# Schematic_easyEDA_-_openELECTRO_-_ARDUIN.net
KiCad netlist of a schematic drawn in EasyEDA
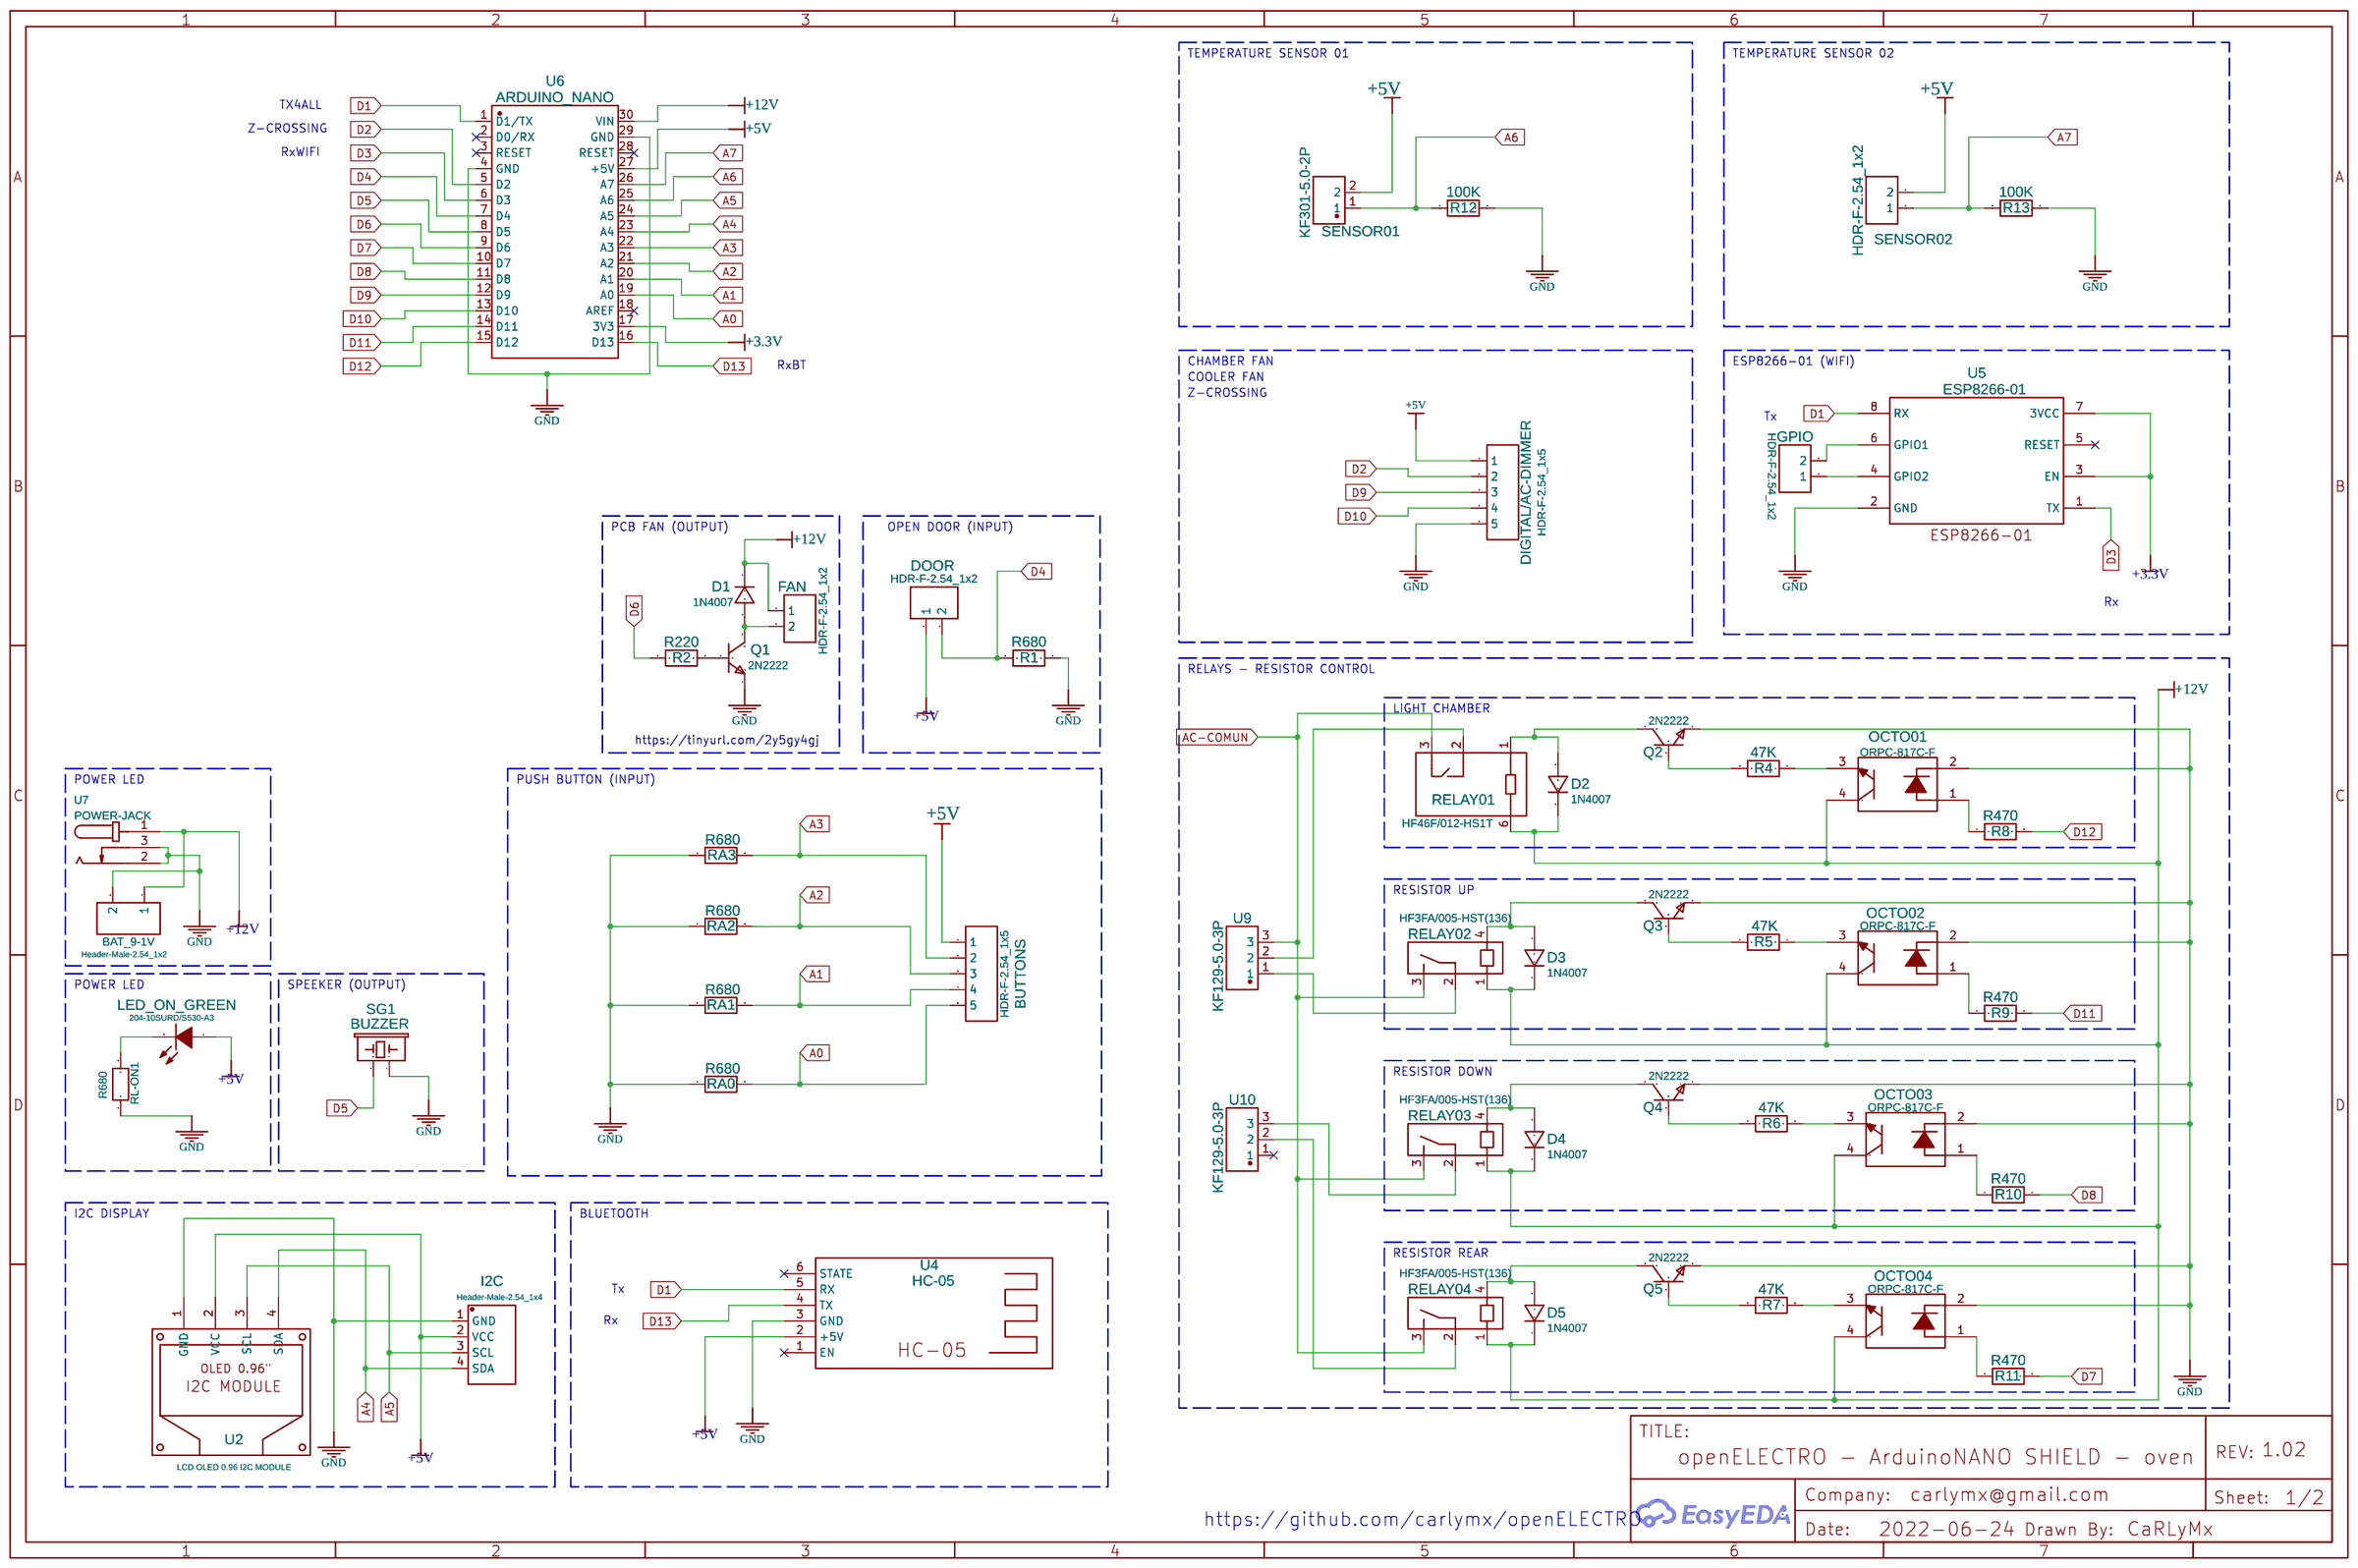
[diagram p0: openELECTRO - ARDUINO NANO SHIELD v1.02]
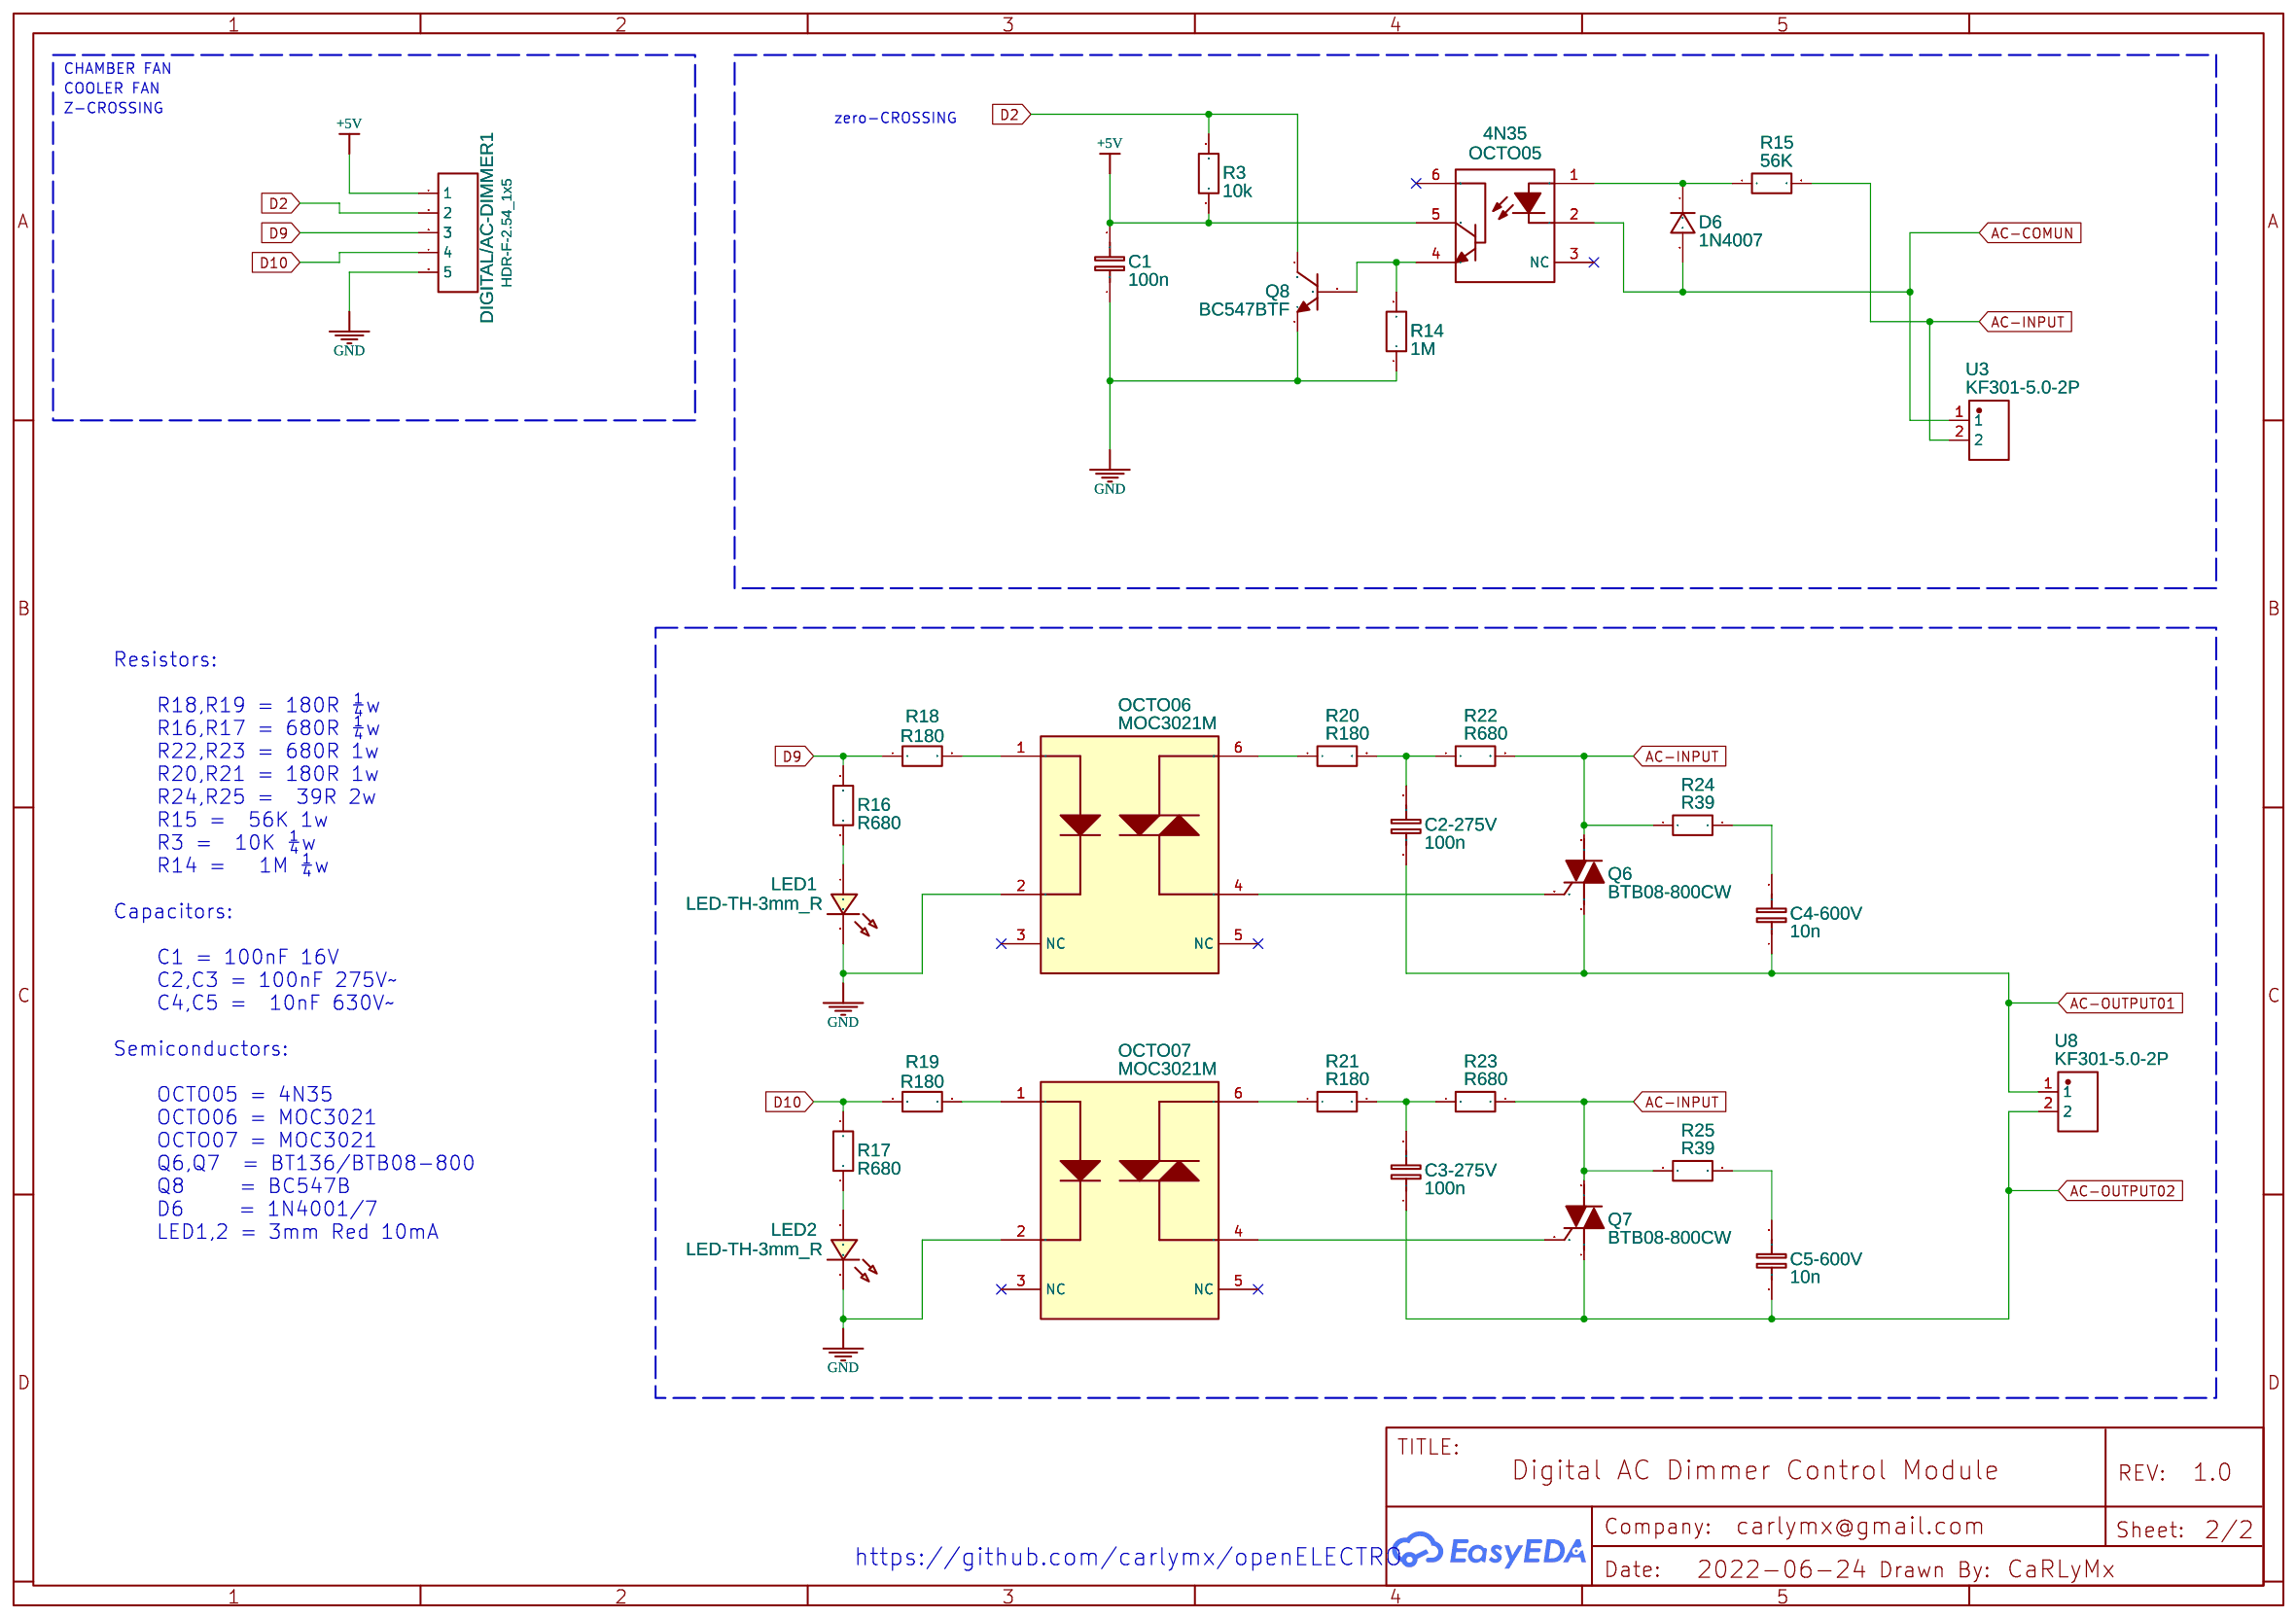
[diagram p1: openELECTRO - Digital AC Dimmer Control v1.0]

(export (version "E")
  (design (tool "Eeschema 10.0.6"))
  (components
    (comp (ref "BAT_9-1V")
      (value "Header-Male-2.54_1x2")
      (fields (field (name "BOM_Manufacturer Part") "826629-2") (field (name "BOM_Supplier Part") "C86471"))
      (libsource (lib "") (part "Unknown_65_-400"))
    )
    (comp (ref "BUTTONS")
      (value "HDR-F-2.54_1x5")
      (fields (field (name "BOM_Supplier Part") "C50950"))
      (libsource (lib "") (part "HDR-F-2.54_1x5"))
    )
    (comp (ref "D1")
      (value "1N4007")
      (fields (field (name "BOM_Supplier Part") "C106903"))
      (libsource (lib "") (part "1N4007_1"))
    )
    (comp (ref "D2")
      (value "1N4007")
      (fields (field (name "BOM_Supplier Part") "C106903"))
      (libsource (lib "") (part "1N4007"))
    )
    (comp (ref "D3")
      (value "1N4007")
      (fields (field (name "BOM_Supplier Part") "C106903"))
      (libsource (lib "") (part "1N4007"))
    )
    (comp (ref "D4")
      (value "1N4007")
      (fields (field (name "BOM_Supplier Part") "C106903"))
      (libsource (lib "") (part "1N4007"))
    )
    (comp (ref "D5")
      (value "1N4007")
      (fields (field (name "BOM_Supplier Part") "C106903"))
      (libsource (lib "") (part "1N4007"))
    )
    (comp (ref "DIGITAL/AC-DIMMER")
      (value "HDR-F-2.54_1x5")
      (fields (field (name "BOM_Supplier Part") "C50950"))
      (libsource (lib "") (part "HDR-F-2.54_1x5_1"))
    )
    (comp (ref "DOOR")
      (value "HDR-F-2.54_1x2")
      (fields (field (name "BOM_Supplier Part") "C49661"))
      (libsource (lib "") (part "HDR-F-2.54_1x2"))
    )
    (comp (ref "FAN")
      (value "HDR-F-2.54_1x2")
      (fields (field (name "BOM_Supplier Part") "C49661"))
      (libsource (lib "") (part "HDR-F-2.54_1x2_1"))
    )
    (comp (ref "GPIO")
      (value "HDR-F-2.54_1x2")
      (fields (field (name "BOM_Supplier Part") "C49661"))
      (libsource (lib "") (part "HDR-F-2.54_1x2_3"))
    )
    (comp (ref "I2C")
      (value "Header-Male-2.54_1x4")
      (fields
        (field (name "BOM_Manufacturer Part") "210S-1*4P L=11.6MMGold-plated black")
        (field (name "BOM_Supplier Part") "C124378")
      )
      (libsource (lib "") (part "Unknown_290_-125"))
    )
    (comp (ref "LED_ON_GREEN")
      (value "204-10SURD/S530-A3")
      (fields (field (name "BOM_Supplier Part") "C99772"))
      (libsource (lib "") (part "Unknown_100_-315"))
    )
    (comp (ref "OCTO01")
      (value "ORPC-817C-F")
      (fields (field (name "BOM_Supplier Part") "C2842770"))
      (libsource (lib "") (part "ORPC-817C-F"))
    )
    (comp (ref "OCTO02")
      (value "ORPC-817C-F")
      (fields (field (name "BOM_Supplier Part") "C2842770"))
      (libsource (lib "") (part "ORPC-817C-F"))
    )
    (comp (ref "OCTO03")
      (value "ORPC-817C-F")
      (fields (field (name "BOM_Supplier Part") "C2842770"))
      (libsource (lib "") (part "ORPC-817C-F"))
    )
    (comp (ref "OCTO04")
      (value "ORPC-817C-F")
      (fields (field (name "BOM_Supplier Part") "C2842770"))
      (libsource (lib "") (part "ORPC-817C-F"))
    )
    (comp (ref "Q1")
      (value "2N2222")
      (fields (field (name "BOM_Supplier Part") "C118536"))
      (libsource (lib "") (part "2N2222_1"))
    )
    (comp (ref "Q2")
      (value "2N2222")
      (fields (field (name "BOM_Supplier Part") "C118536"))
      (libsource (lib "") (part "2N2222"))
    )
    (comp (ref "Q3")
      (value "2N2222")
      (fields (field (name "BOM_Supplier Part") "C118536"))
      (libsource (lib "") (part "2N2222"))
    )
    (comp (ref "Q4")
      (value "2N2222")
      (fields (field (name "BOM_Supplier Part") "C118536"))
      (libsource (lib "") (part "2N2222"))
    )
    (comp (ref "Q5")
      (value "2N2222")
      (fields (field (name "BOM_Supplier Part") "C118536"))
      (libsource (lib "") (part "2N2222"))
    )
    (comp (ref "R1") (value "R680") (libsource (lib "") (part "R_0603_EU_1")))
    (comp (ref "R2") (value "R220") (libsource (lib "") (part "R_0603_EU")))
    (comp (ref "R4") (value "47K") (libsource (lib "") (part "R_0603_EU_1")))
    (comp (ref "R5") (value "47K") (libsource (lib "") (part "R_0603_EU")))
    (comp (ref "R6") (value "47K") (libsource (lib "") (part "R_0603_EU")))
    (comp (ref "R7") (value "47K") (libsource (lib "") (part "R_0603_EU")))
    (comp (ref "R8") (value "R470") (libsource (lib "") (part "R_0603_EU")))
    (comp (ref "R9") (value "R470") (libsource (lib "") (part "R_0603_EU")))
    (comp (ref "R10") (value "R470") (libsource (lib "") (part "R_0603_EU")))
    (comp (ref "R11") (value "R470") (libsource (lib "") (part "R_0603_EU")))
    (comp (ref "R12") (value "100K") (libsource (lib "") (part "R_0603_EU")))
    (comp (ref "R13") (value "100K") (libsource (lib "") (part "R_0603_EU")))
    (comp (ref "RA0") (value "R680") (libsource (lib "") (part "Res_AXIAL-0.3(1/8W)_EU")))
    (comp (ref "RA1") (value "R680") (libsource (lib "") (part "Res_AXIAL-0.3(1/8W)_EU")))
    (comp (ref "RA2") (value "R680") (libsource (lib "") (part "Res_AXIAL-0.3(1/8W)_EU")))
    (comp (ref "RA3") (value "R680") (libsource (lib "") (part "Res_AXIAL-0.3(1/8W)_EU")))
    (comp (ref "RELAY01")
      (value "HF46F/012-HS1T")
      (fields (field (name "BOM_Supplier Part") "C2976852"))
      (libsource (lib "") (part "HF46F/012-HS1T"))
    )
    (comp (ref "RELAY02")
      (value "HF3FA/005-HST(136)")
      (fields (field (name "BOM_Supplier Part") "C712707"))
      (libsource (lib "") (part "HF3FA/005-HST(136)"))
    )
    (comp (ref "RELAY03")
      (value "HF3FA/005-HST(136)")
      (fields (field (name "BOM_Supplier Part") "C712707"))
      (libsource (lib "") (part "HF3FA/005-HST(136)"))
    )
    (comp (ref "RELAY04")
      (value "HF3FA/005-HST(136)")
      (fields (field (name "BOM_Supplier Part") "C712707"))
      (libsource (lib "") (part "HF3FA/005-HST(136)"))
    )
    (comp (ref "RL-ON1") (value "R680") (libsource (lib "") (part "Res_AXIAL-0.3(1/8W)_EU_1")))
    (comp (ref "SENSOR01")
      (value "KF301-5.0-2P")
      (fields (field (name "BOM_Supplier Part") "C474881"))
      (libsource (lib "") (part "KF301-5.0-2P"))
    )
    (comp (ref "SENSOR02")
      (value "HDR-F-2.54_1x2")
      (fields (field (name "BOM_Supplier Part") "C49661"))
      (libsource (lib "") (part "HDR-F-2.54_1x2_2"))
    )
    (comp (ref "SG1") (value "BUZZER") (libsource (lib "") (part "Unknown_225_-305")))
    (comp (ref "U2")
      (value "LCD OLED 0.96 I2C MODULE")
      (fields (field (name "BOM_Manufacturer Part") "Control Chip SSD1306"))
      (libsource (lib "") (part "Unknown_80_-135"))
    )
    (comp (ref "U4") (value "HC-05") (libsource (lib "") (part "Unknown_500_-180")))
    (comp (ref "U5") (value "ESP8266-01") (libsource (lib "") (part "ESP8266-01")))
    (comp (ref "U6")
      (value "ARDUINO_NANO")
      (fields (field (name "BOM_Supplier Part") "C9900017879"))
      (libsource (lib "") (part "ARDUINO_NANO"))
    )
    (comp (ref "U7")
      (value "POWER-JACK")
      (fields (field (name "BOM_Supplier Part") "C9900001795"))
      (libsource (lib "") (part "POWER-JACK"))
    )
    (comp (ref "U9")
      (value "KF129-5.0-3P")
      (fields (field (name "BOM_Supplier Part") "C475091"))
      (libsource (lib "") (part "KF129-5.0-3P"))
    )
    (comp (ref "U10")
      (value "KF129-5.0-3P")
      (fields (field (name "BOM_Supplier Part") "C475091"))
      (libsource (lib "") (part "KF129-5.0-3P"))
    )
    (comp (ref "C1") (value "100n") (libsource (lib "") (part "C_0603_EU_1")))
    (comp (ref "C2-275V") (value "100n") (libsource (lib "") (part "C_0603_EU_4")))
    (comp (ref "C3-275V") (value "100n") (libsource (lib "") (part "C_0603_EU")))
    (comp (ref "C4-600V") (value "10n") (libsource (lib "") (part "C_0603_EU_2")))
    (comp (ref "C5-600V") (value "10n") (libsource (lib "") (part "C_0603_EU_3")))
    (comp (ref "D6")
      (value "1N4007")
      (fields (field (name "BOM_Supplier Part") "C106903"))
      (libsource (lib "") (part "1N4007"))
    )
    (comp (ref "DIGITAL/AC-DIMMER1")
      (value "HDR-F-2.54_1x5")
      (fields (field (name "BOM_Supplier Part") "C50950"))
      (libsource (lib "") (part "HDR-F-2.54_1x5"))
    )
    (comp (ref "LED1")
      (value "LED-TH-3mm_R")
      (fields
        (field (name "BOM_Manufacturer Part") "204-10SDRD/S530-A3-L")
        (field (name "BOM_Supplier Part") "C84774")
      )
      (libsource (lib "") (part "LED-TH-3mm_R"))
    )
    (comp (ref "LED2")
      (value "LED-TH-3mm_R")
      (fields
        (field (name "BOM_Manufacturer Part") "204-10SDRD/S530-A3-L")
        (field (name "BOM_Supplier Part") "C84774")
      )
      (libsource (lib "") (part "LED-TH-3mm_R"))
    )
    (comp (ref "OCTO05")
      (value "4N35")
      (fields (field (name "BOM_Supplier Part") "C57084"))
      (libsource (lib "") (part "4N35"))
    )
    (comp (ref "OCTO06")
      (value "MOC3021M")
      (fields (field (name "BOM_Supplier Part") "C5242"))
      (libsource (lib "") (part "MOC3021M"))
    )
    (comp (ref "OCTO07")
      (value "MOC3021M")
      (fields (field (name "BOM_Supplier Part") "C5242"))
      (libsource (lib "") (part "MOC3021M"))
    )
    (comp (ref "Q6")
      (value "BTB08-800CW")
      (fields (field (name "BOM_Supplier Part") "C2900905"))
      (libsource (lib "") (part "BTB08-800CW"))
    )
    (comp (ref "Q7")
      (value "BTB08-800CW")
      (fields (field (name "BOM_Supplier Part") "C2900905"))
      (libsource (lib "") (part "BTB08-800CW"))
    )
    (comp (ref "Q8")
      (value "BC547BTF")
      (fields (field (name "BOM_Supplier Part") "C900798"))
      (libsource (lib "") (part "BC547BTF"))
    )
    (comp (ref "R3") (value "10k") (libsource (lib "") (part "R_AXIAL-0.3_EU_1")))
    (comp (ref "R14") (value "1M") (libsource (lib "") (part "R_AXIAL-0.3_EU_1")))
    (comp (ref "R15") (value "56K") (libsource (lib "") (part "R_AXIAL-0.3_EU")))
    (comp (ref "R16") (value "R680") (libsource (lib "") (part "R_AXIAL-0.3_EU_1")))
    (comp (ref "R17") (value "R680") (libsource (lib "") (part "R_AXIAL-0.3_EU_1")))
    (comp (ref "R18") (value "R180") (libsource (lib "") (part "R_AXIAL-0.3_EU")))
    (comp (ref "R19") (value "R180") (libsource (lib "") (part "R_AXIAL-0.3_EU")))
    (comp (ref "R20") (value "R180") (libsource (lib "") (part "R_AXIAL-0.3_EU")))
    (comp (ref "R21") (value "R180") (libsource (lib "") (part "R_AXIAL-0.3_EU")))
    (comp (ref "R22") (value "R680") (libsource (lib "") (part "R_AXIAL-0.3_EU")))
    (comp (ref "R23") (value "R680") (libsource (lib "") (part "R_AXIAL-0.3_EU")))
    (comp (ref "R24") (value "R39") (libsource (lib "") (part "R_AXIAL-0.3_EU")))
    (comp (ref "R25") (value "R39") (libsource (lib "") (part "R_AXIAL-0.3_EU")))
    (comp (ref "U3")
      (value "KF301-5.0-2P")
      (fields (field (name "BOM_Supplier Part") "C474881"))
      (libsource (lib "") (part "KF301-5.0-2P"))
    )
    (comp (ref "U8")
      (value "KF301-5.0-2P")
      (fields (field (name "BOM_Supplier Part") "C474881"))
      (libsource (lib "") (part "KF301-5.0-2P"))
    )
  )
  (nets
    (net (code "1") (name "+3.3V") (class "Default")
      (node (ref "U5") (pin "3") (pinfunction "EN_3") (pintype "unspecified"))
      (node (ref "U5") (pin "7") (pinfunction "3VCC_7") (pintype "unspecified"))
      (node (ref "U6") (pin "17") (pinfunction "3V3_17") (pintype "unspecified"))
    )
    (net (code "2") (name "+5V") (class "Default")
      (node (ref "BUTTONS") (pin "1") (pinfunction "1_1") (pintype "unspecified"))
      (node (ref "C1") (pin "2") (pinfunction "2_2") (pintype "unspecified"))
      (node (ref "DIGITAL/AC-DIMMER") (pin "1") (pinfunction "1_1") (pintype "unspecified"))
      (node (ref "DIGITAL/AC-DIMMER1") (pin "1") (pinfunction "1_1") (pintype "unspecified"))
      (node (ref "DOOR") (pin "1") (pinfunction "1_1") (pintype "input"))
      (node (ref "I2C") (pin "2") (pinfunction "VCC_2") (pintype "unspecified"))
      (node (ref "LED_ON_GREEN") (pin "1") (pinfunction "A_1") (pintype "unspecified"))
      (node (ref "OCTO05") (pin "5") (pinfunction "5_5") (pintype "unspecified"))
      (node (ref "R3") (pin "1") (pinfunction "1_1") (pintype "unspecified"))
      (node (ref "SENSOR01") (pin "2") (pinfunction "2_2") (pintype "unspecified"))
      (node (ref "SENSOR02") (pin "2") (pinfunction "2_2") (pintype "input"))
      (node (ref "U2") (pin "2") (pinfunction "VCC_2") (pintype "unspecified"))
      (node (ref "U4") (pin "2") (pinfunction "+5V_2") (pintype "unspecified"))
      (node (ref "U6") (pin "27") (pinfunction "+5V_27") (pintype "unspecified"))
    )
    (net (code "3") (name "+12V") (class "Default")
      (node (ref "BAT_9-1V") (pin "1") (pinfunction "1_1") (pintype "unspecified"))
      (node (ref "D1") (pin "1") (pinfunction "1_1") (pintype "unspecified"))
      (node (ref "D2") (pin "1") (pinfunction "1_1") (pintype "unspecified"))
      (node (ref "D3") (pin "1") (pinfunction "1_1") (pintype "unspecified"))
      (node (ref "D4") (pin "1") (pinfunction "1_1") (pintype "unspecified"))
      (node (ref "D5") (pin "1") (pinfunction "1_1") (pintype "unspecified"))
      (node (ref "FAN") (pin "1") (pinfunction "1_1") (pintype "input"))
      (node (ref "OCTO01") (pin "4") (pinfunction "4_4") (pintype "unspecified"))
      (node (ref "OCTO02") (pin "4") (pinfunction "4_4") (pintype "unspecified"))
      (node (ref "OCTO03") (pin "4") (pinfunction "4_4") (pintype "unspecified"))
      (node (ref "OCTO04") (pin "4") (pinfunction "4_4") (pintype "unspecified"))
      (node (ref "RELAY01") (pin "6") (pinfunction "6_6") (pintype "unspecified"))
      (node (ref "RELAY02") (pin "1") (pinfunction "1_1") (pintype "unspecified"))
      (node (ref "RELAY03") (pin "1") (pinfunction "1_1") (pintype "unspecified"))
      (node (ref "RELAY04") (pin "1") (pinfunction "1_1") (pintype "unspecified"))
      (node (ref "U6") (pin "30") (pinfunction "VIN_30") (pintype "unspecified"))
      (node (ref "U7") (pin "1") (pinfunction "1_1") (pintype "unspecified"))
    )
    (net (code "4") (name "A0") (class "Default")
      (node (ref "BUTTONS") (pin "5") (pinfunction "5_5") (pintype "unspecified"))
      (node (ref "RA0") (pin "2") (pinfunction "2_2") (pintype "unspecified"))
      (node (ref "U6") (pin "19") (pinfunction "A0_19") (pintype "unspecified"))
    )
    (net (code "5") (name "A1") (class "Default")
      (node (ref "BUTTONS") (pin "4") (pinfunction "4_4") (pintype "unspecified"))
      (node (ref "RA1") (pin "2") (pinfunction "2_2") (pintype "unspecified"))
      (node (ref "U6") (pin "20") (pinfunction "A1_20") (pintype "unspecified"))
    )
    (net (code "6") (name "A2") (class "Default")
      (node (ref "BUTTONS") (pin "3") (pinfunction "3_3") (pintype "unspecified"))
      (node (ref "RA2") (pin "2") (pinfunction "2_2") (pintype "unspecified"))
      (node (ref "U6") (pin "21") (pinfunction "A2_21") (pintype "unspecified"))
    )
    (net (code "7") (name "A3") (class "Default")
      (node (ref "BUTTONS") (pin "2") (pinfunction "2_2") (pintype "unspecified"))
      (node (ref "RA3") (pin "2") (pinfunction "2_2") (pintype "unspecified"))
      (node (ref "U6") (pin "22") (pinfunction "A3_22") (pintype "unspecified"))
    )
    (net (code "8") (name "A4") (class "Default")
      (node (ref "I2C") (pin "4") (pinfunction "SDA_4") (pintype "unspecified"))
      (node (ref "U2") (pin "4") (pinfunction "SDA_4") (pintype "unspecified"))
      (node (ref "U6") (pin "23") (pinfunction "A4_23") (pintype "unspecified"))
    )
    (net (code "9") (name "A5") (class "Default")
      (node (ref "I2C") (pin "3") (pinfunction "SCL_3") (pintype "unspecified"))
      (node (ref "U2") (pin "3") (pinfunction "SCL_3") (pintype "unspecified"))
      (node (ref "U6") (pin "24") (pinfunction "A5_24") (pintype "unspecified"))
    )
    (net (code "10") (name "A6") (class "Default")
      (node (ref "R12") (pin "1") (pinfunction "1_1") (pintype "unspecified"))
      (node (ref "SENSOR01") (pin "1") (pinfunction "1_1") (pintype "unspecified"))
      (node (ref "U6") (pin "25") (pinfunction "A6_25") (pintype "unspecified"))
    )
    (net (code "11") (name "A7") (class "Default")
      (node (ref "R13") (pin "1") (pinfunction "1_1") (pintype "unspecified"))
      (node (ref "SENSOR02") (pin "1") (pinfunction "1_1") (pintype "input"))
      (node (ref "U6") (pin "26") (pinfunction "A7_26") (pintype "unspecified"))
    )
    (net (code "12") (name "AC-COMUN") (class "Default")
      (node (ref "D6") (pin "2") (pinfunction "2_2") (pintype "unspecified"))
      (node (ref "OCTO05") (pin "2") (pinfunction "2_2") (pintype "unspecified"))
      (node (ref "RELAY01") (pin "3") (pinfunction "3_3") (pintype "unspecified"))
      (node (ref "RELAY02") (pin "3") (pinfunction "3_3") (pintype "unspecified"))
      (node (ref "RELAY03") (pin "3") (pinfunction "3_3") (pintype "unspecified"))
      (node (ref "RELAY04") (pin "3") (pinfunction "3_3") (pintype "unspecified"))
      (node (ref "U3") (pin "1") (pinfunction "1_1") (pintype "unspecified"))
      (node (ref "U9") (pin "3") (pinfunction "3_3") (pintype "unspecified"))
    )
    (net (code "13") (name "AC-INPUT") (class "Default")
      (node (ref "Q6") (pin "2") (pinfunction "T2_2") (pintype "unspecified"))
      (node (ref "Q7") (pin "2") (pinfunction "T2_2") (pintype "unspecified"))
      (node (ref "R15") (pin "2") (pinfunction "2_2") (pintype "unspecified"))
      (node (ref "R22") (pin "2") (pinfunction "2_2") (pintype "unspecified"))
      (node (ref "R23") (pin "2") (pinfunction "2_2") (pintype "unspecified"))
      (node (ref "R24") (pin "1") (pinfunction "1_1") (pintype "unspecified"))
      (node (ref "R25") (pin "1") (pinfunction "1_1") (pintype "unspecified"))
      (node (ref "U3") (pin "2") (pinfunction "2_2") (pintype "unspecified"))
    )
    (net (code "14") (name "AC-OUTPUT01") (class "Default")
      (node (ref "C2-275V") (pin "1") (pinfunction "1_1") (pintype "unspecified"))
      (node (ref "C4-600V") (pin "1") (pinfunction "1_1") (pintype "unspecified"))
      (node (ref "Q6") (pin "1") (pinfunction "T1_1") (pintype "unspecified"))
      (node (ref "U8") (pin "1") (pinfunction "1_1") (pintype "unspecified"))
    )
    (net (code "15") (name "AC-OUTPUT02") (class "Default")
      (node (ref "C3-275V") (pin "1") (pinfunction "1_1") (pintype "unspecified"))
      (node (ref "C5-600V") (pin "1") (pinfunction "1_1") (pintype "unspecified"))
      (node (ref "Q7") (pin "1") (pinfunction "T1_1") (pintype "unspecified"))
      (node (ref "U8") (pin "2") (pinfunction "2_2") (pintype "unspecified"))
    )
    (net (code "16") (name "D1") (class "Default")
      (node (ref "U4") (pin "5") (pinfunction "RX_5") (pintype "unspecified"))
      (node (ref "U5") (pin "8") (pinfunction "RX_8") (pintype "unspecified"))
      (node (ref "U6") (pin "1") (pinfunction "D1/TX_1") (pintype "unspecified"))
    )
    (net (code "17") (name "D2") (class "Default")
      (node (ref "DIGITAL/AC-DIMMER") (pin "2") (pinfunction "2_2") (pintype "unspecified"))
      (node (ref "DIGITAL/AC-DIMMER1") (pin "2") (pinfunction "2_2") (pintype "unspecified"))
      (node (ref "Q8") (pin "1") (pinfunction "C_1") (pintype "unspecified"))
      (node (ref "R3") (pin "2") (pinfunction "2_2") (pintype "unspecified"))
      (node (ref "U6") (pin "5") (pinfunction "D2_5") (pintype "unspecified"))
    )
    (net (code "18") (name "D3") (class "Default")
      (node (ref "U5") (pin "1") (pinfunction "TX_1") (pintype "unspecified"))
      (node (ref "U6") (pin "6") (pinfunction "D3_6") (pintype "unspecified"))
    )
    (net (code "19") (name "D4") (class "Default")
      (node (ref "DOOR") (pin "2") (pinfunction "2_2") (pintype "input"))
      (node (ref "R1") (pin "2") (pinfunction "2_2") (pintype "unspecified"))
      (node (ref "U6") (pin "7") (pinfunction "D4_7") (pintype "unspecified"))
    )
    (net (code "20") (name "D5") (class "Default")
      (node (ref "SG1") (pin "+") (pinfunction "1_+") (pintype "unspecified"))
      (node (ref "U6") (pin "8") (pinfunction "D5_8") (pintype "unspecified"))
    )
    (net (code "21") (name "D6") (class "Default")
      (node (ref "R2") (pin "1") (pinfunction "1_1") (pintype "unspecified"))
      (node (ref "U6") (pin "9") (pinfunction "D6_9") (pintype "unspecified"))
    )
    (net (code "22") (name "D7") (class "Default")
      (node (ref "R11") (pin "2") (pinfunction "2_2") (pintype "unspecified"))
      (node (ref "U6") (pin "10") (pinfunction "D7_10") (pintype "unspecified"))
    )
    (net (code "23") (name "D8") (class "Default")
      (node (ref "R10") (pin "2") (pinfunction "2_2") (pintype "unspecified"))
      (node (ref "U6") (pin "11") (pinfunction "D8_11") (pintype "unspecified"))
    )
    (net (code "24") (name "D9") (class "Default")
      (node (ref "DIGITAL/AC-DIMMER") (pin "3") (pinfunction "3_3") (pintype "unspecified"))
      (node (ref "DIGITAL/AC-DIMMER1") (pin "3") (pinfunction "3_3") (pintype "unspecified"))
      (node (ref "R16") (pin "2") (pinfunction "2_2") (pintype "unspecified"))
      (node (ref "R18") (pin "1") (pinfunction "1_1") (pintype "unspecified"))
      (node (ref "U6") (pin "12") (pinfunction "D9_12") (pintype "unspecified"))
    )
    (net (code "25") (name "D10") (class "Default")
      (node (ref "DIGITAL/AC-DIMMER") (pin "4") (pinfunction "4_4") (pintype "unspecified"))
      (node (ref "DIGITAL/AC-DIMMER1") (pin "4") (pinfunction "4_4") (pintype "unspecified"))
      (node (ref "R17") (pin "2") (pinfunction "2_2") (pintype "unspecified"))
      (node (ref "R19") (pin "1") (pinfunction "1_1") (pintype "unspecified"))
      (node (ref "U6") (pin "13") (pinfunction "D10_13") (pintype "unspecified"))
    )
    (net (code "26") (name "D11") (class "Default")
      (node (ref "R9") (pin "2") (pinfunction "2_2") (pintype "unspecified"))
      (node (ref "U6") (pin "14") (pinfunction "D11_14") (pintype "unspecified"))
    )
    (net (code "27") (name "D12") (class "Default")
      (node (ref "R8") (pin "2") (pinfunction "2_2") (pintype "unspecified"))
      (node (ref "U6") (pin "15") (pinfunction "D12_15") (pintype "unspecified"))
    )
    (net (code "28") (name "D13") (class "Default")
      (node (ref "U4") (pin "4") (pinfunction "TX_4") (pintype "unspecified"))
      (node (ref "U6") (pin "16") (pinfunction "D13_16") (pintype "unspecified"))
    )
    (net (code "29") (name "GND") (class "Default")
      (node (ref "BAT_9-1V") (pin "2") (pinfunction "2_2") (pintype "unspecified"))
      (node (ref "C1") (pin "1") (pinfunction "1_1") (pintype "unspecified"))
      (node (ref "DIGITAL/AC-DIMMER") (pin "5") (pinfunction "5_5") (pintype "unspecified"))
      (node (ref "DIGITAL/AC-DIMMER1") (pin "5") (pinfunction "5_5") (pintype "unspecified"))
      (node (ref "I2C") (pin "1") (pinfunction "GND_1") (pintype "unspecified"))
      (node (ref "LED1") (pin "2") (pinfunction "2_2") (pintype "unspecified"))
      (node (ref "LED2") (pin "2") (pinfunction "2_2") (pintype "unspecified"))
      (node (ref "OCTO01") (pin "2") (pinfunction "2_2") (pintype "unspecified"))
      (node (ref "OCTO02") (pin "2") (pinfunction "2_2") (pintype "unspecified"))
      (node (ref "OCTO03") (pin "2") (pinfunction "2_2") (pintype "unspecified"))
      (node (ref "OCTO04") (pin "2") (pinfunction "2_2") (pintype "unspecified"))
      (node (ref "OCTO06") (pin "2") (pinfunction "2_2") (pintype "input"))
      (node (ref "OCTO07") (pin "2") (pinfunction "2_2") (pintype "input"))
      (node (ref "Q1") (pin "1") (pinfunction "E_1") (pintype "unspecified"))
      (node (ref "Q2") (pin "1") (pinfunction "E_1") (pintype "unspecified"))
      (node (ref "Q3") (pin "1") (pinfunction "E_1") (pintype "unspecified"))
      (node (ref "Q4") (pin "1") (pinfunction "E_1") (pintype "unspecified"))
      (node (ref "Q5") (pin "1") (pinfunction "E_1") (pintype "unspecified"))
      (node (ref "Q8") (pin "3") (pinfunction "E_3") (pintype "unspecified"))
      (node (ref "R1") (pin "1") (pinfunction "1_1") (pintype "unspecified"))
      (node (ref "R12") (pin "2") (pinfunction "2_2") (pintype "unspecified"))
      (node (ref "R13") (pin "2") (pinfunction "2_2") (pintype "unspecified"))
      (node (ref "R14") (pin "1") (pinfunction "1_1") (pintype "unspecified"))
      (node (ref "RA0") (pin "1") (pinfunction "1_1") (pintype "unspecified"))
      (node (ref "RA1") (pin "1") (pinfunction "1_1") (pintype "unspecified"))
      (node (ref "RA2") (pin "1") (pinfunction "1_1") (pintype "unspecified"))
      (node (ref "RA3") (pin "1") (pinfunction "1_1") (pintype "unspecified"))
      (node (ref "RL-ON1") (pin "1") (pinfunction "1_1") (pintype "unspecified"))
      (node (ref "SG1") (pin "-") (pinfunction "2_-") (pintype "unspecified"))
      (node (ref "U2") (pin "1") (pinfunction "GND_1") (pintype "unspecified"))
      (node (ref "U4") (pin "3") (pinfunction "GND_3") (pintype "unspecified"))
      (node (ref "U5") (pin "2") (pinfunction "GND_2") (pintype "unspecified"))
      (node (ref "U6") (pin "29") (pinfunction "GND_29") (pintype "unspecified"))
      (node (ref "U6") (pin "4") (pinfunction "GND_4") (pintype "unspecified"))
      (node (ref "U7") (pin "2") (pinfunction "2_2") (pintype "unspecified"))
      (node (ref "U7") (pin "3") (pinfunction "3_3") (pintype "unspecified"))
    )
    (net (code "30") (name "Net-(C2-275V-Pad2)") (class "Default")
      (node (ref "C2-275V") (pin "2") (pinfunction "2_2") (pintype "unspecified"))
      (node (ref "R20") (pin "2") (pinfunction "2_2") (pintype "unspecified"))
      (node (ref "R22") (pin "1") (pinfunction "1_1") (pintype "unspecified"))
    )
    (net (code "31") (name "Net-(C3-275V-Pad2)") (class "Default")
      (node (ref "C3-275V") (pin "2") (pinfunction "2_2") (pintype "unspecified"))
      (node (ref "R21") (pin "2") (pinfunction "2_2") (pintype "unspecified"))
      (node (ref "R23") (pin "1") (pinfunction "1_1") (pintype "unspecified"))
    )
    (net (code "32") (name "Net-(C4-600V-Pad2)") (class "Default")
      (node (ref "C4-600V") (pin "2") (pinfunction "2_2") (pintype "unspecified"))
      (node (ref "R24") (pin "2") (pinfunction "2_2") (pintype "unspecified"))
    )
    (net (code "33") (name "Net-(C5-600V-Pad2)") (class "Default")
      (node (ref "C5-600V") (pin "2") (pinfunction "2_2") (pintype "unspecified"))
      (node (ref "R25") (pin "2") (pinfunction "2_2") (pintype "unspecified"))
    )
    (net (code "34") (name "Net-(D6-Pad1)") (class "Default")
      (node (ref "D6") (pin "1") (pinfunction "1_1") (pintype "unspecified"))
      (node (ref "OCTO05") (pin "1") (pinfunction "1_1") (pintype "unspecified"))
      (node (ref "R15") (pin "1") (pinfunction "1_1") (pintype "unspecified"))
    )
    (net (code "35") (name "Net-(LED1-Pad1)") (class "Default")
      (node (ref "LED1") (pin "1") (pinfunction "1_1") (pintype "unspecified"))
      (node (ref "R16") (pin "1") (pinfunction "1_1") (pintype "unspecified"))
    )
    (net (code "36") (name "Net-(LED2-Pad1)") (class "Default")
      (node (ref "LED2") (pin "1") (pinfunction "1_1") (pintype "unspecified"))
      (node (ref "R17") (pin "1") (pinfunction "1_1") (pintype "unspecified"))
    )
    (net (code "37") (name "Net-(LED_ON_GREEN-K)") (class "Default")
      (node (ref "LED_ON_GREEN") (pin "2") (pinfunction "K_2") (pintype "unspecified"))
      (node (ref "RL-ON1") (pin "2") (pinfunction "2_2") (pintype "unspecified"))
    )
    (net (code "38") (name "Net-(OCTO01-Pad1)") (class "Default")
      (node (ref "OCTO01") (pin "1") (pinfunction "1_1") (pintype "unspecified"))
      (node (ref "R8") (pin "1") (pinfunction "1_1") (pintype "unspecified"))
    )
    (net (code "39") (name "Net-(OCTO01-Pad3)") (class "Default")
      (node (ref "OCTO01") (pin "3") (pinfunction "3_3") (pintype "unspecified"))
      (node (ref "R4") (pin "1") (pinfunction "1_1") (pintype "unspecified"))
    )
    (net (code "40") (name "Net-(OCTO02-Pad1)") (class "Default")
      (node (ref "OCTO02") (pin "1") (pinfunction "1_1") (pintype "unspecified"))
      (node (ref "R9") (pin "1") (pinfunction "1_1") (pintype "unspecified"))
    )
    (net (code "41") (name "Net-(OCTO02-Pad3)") (class "Default")
      (node (ref "OCTO02") (pin "3") (pinfunction "3_3") (pintype "unspecified"))
      (node (ref "R5") (pin "2") (pinfunction "2_2") (pintype "unspecified"))
    )
    (net (code "42") (name "Net-(OCTO03-Pad1)") (class "Default")
      (node (ref "OCTO03") (pin "1") (pinfunction "1_1") (pintype "unspecified"))
      (node (ref "R10") (pin "1") (pinfunction "1_1") (pintype "unspecified"))
    )
    (net (code "43") (name "Net-(OCTO03-Pad3)") (class "Default")
      (node (ref "OCTO03") (pin "3") (pinfunction "3_3") (pintype "unspecified"))
      (node (ref "R6") (pin "2") (pinfunction "2_2") (pintype "unspecified"))
    )
    (net (code "44") (name "Net-(OCTO04-Pad1)") (class "Default")
      (node (ref "OCTO04") (pin "1") (pinfunction "1_1") (pintype "unspecified"))
      (node (ref "R11") (pin "1") (pinfunction "1_1") (pintype "unspecified"))
    )
    (net (code "45") (name "Net-(OCTO04-Pad3)") (class "Default")
      (node (ref "OCTO04") (pin "3") (pinfunction "3_3") (pintype "unspecified"))
      (node (ref "R7") (pin "2") (pinfunction "2_2") (pintype "unspecified"))
    )
    (net (code "46") (name "Net-(OCTO06-Pad1)") (class "Default")
      (node (ref "OCTO06") (pin "1") (pinfunction "1_1") (pintype "input"))
      (node (ref "R18") (pin "2") (pinfunction "2_2") (pintype "unspecified"))
    )
    (net (code "47") (name "Net-(OCTO06-Pad6)") (class "Default")
      (node (ref "OCTO06") (pin "6") (pinfunction "6_6") (pintype "input"))
      (node (ref "R20") (pin "1") (pinfunction "1_1") (pintype "unspecified"))
    )
    (net (code "48") (name "Net-(OCTO07-Pad1)") (class "Default")
      (node (ref "OCTO07") (pin "1") (pinfunction "1_1") (pintype "input"))
      (node (ref "R19") (pin "2") (pinfunction "2_2") (pintype "unspecified"))
    )
    (net (code "49") (name "Net-(OCTO07-Pad6)") (class "Default")
      (node (ref "OCTO07") (pin "6") (pinfunction "6_6") (pintype "input"))
      (node (ref "R21") (pin "1") (pinfunction "1_1") (pintype "unspecified"))
    )
    (net (code "50") (name "Net-(Q1-B)") (class "Default")
      (node (ref "Q1") (pin "2") (pinfunction "B_2") (pintype "unspecified"))
      (node (ref "R2") (pin "2") (pinfunction "2_2") (pintype "unspecified"))
    )
    (net (code "51") (name "Net-(Q1-C)") (class "Default")
      (node (ref "D1") (pin "2") (pinfunction "2_2") (pintype "unspecified"))
      (node (ref "FAN") (pin "2") (pinfunction "2_2") (pintype "input"))
      (node (ref "Q1") (pin "3") (pinfunction "C_3") (pintype "unspecified"))
    )
    (net (code "52") (name "Net-(Q2-B)") (class "Default")
      (node (ref "Q2") (pin "2") (pinfunction "B_2") (pintype "unspecified"))
      (node (ref "R4") (pin "2") (pinfunction "2_2") (pintype "unspecified"))
    )
    (net (code "53") (name "Net-(Q2-C)") (class "Default")
      (node (ref "D2") (pin "2") (pinfunction "2_2") (pintype "unspecified"))
      (node (ref "Q2") (pin "3") (pinfunction "C_3") (pintype "unspecified"))
      (node (ref "RELAY01") (pin "1") (pinfunction "1_1") (pintype "unspecified"))
    )
    (net (code "54") (name "Net-(Q3-B)") (class "Default")
      (node (ref "Q3") (pin "2") (pinfunction "B_2") (pintype "unspecified"))
      (node (ref "R5") (pin "1") (pinfunction "1_1") (pintype "unspecified"))
    )
    (net (code "55") (name "Net-(Q3-C)") (class "Default")
      (node (ref "D3") (pin "2") (pinfunction "2_2") (pintype "unspecified"))
      (node (ref "Q3") (pin "3") (pinfunction "C_3") (pintype "unspecified"))
      (node (ref "RELAY02") (pin "4") (pinfunction "4_4") (pintype "unspecified"))
    )
    (net (code "56") (name "Net-(Q4-B)") (class "Default")
      (node (ref "Q4") (pin "2") (pinfunction "B_2") (pintype "unspecified"))
      (node (ref "R6") (pin "1") (pinfunction "1_1") (pintype "unspecified"))
    )
    (net (code "57") (name "Net-(Q4-C)") (class "Default")
      (node (ref "D4") (pin "2") (pinfunction "2_2") (pintype "unspecified"))
      (node (ref "Q4") (pin "3") (pinfunction "C_3") (pintype "unspecified"))
      (node (ref "RELAY03") (pin "4") (pinfunction "4_4") (pintype "unspecified"))
    )
    (net (code "58") (name "Net-(Q5-B)") (class "Default")
      (node (ref "Q5") (pin "2") (pinfunction "B_2") (pintype "unspecified"))
      (node (ref "R7") (pin "1") (pinfunction "1_1") (pintype "unspecified"))
    )
    (net (code "59") (name "Net-(Q5-C)") (class "Default")
      (node (ref "D5") (pin "2") (pinfunction "2_2") (pintype "unspecified"))
      (node (ref "Q5") (pin "3") (pinfunction "C_3") (pintype "unspecified"))
      (node (ref "RELAY04") (pin "4") (pinfunction "4_4") (pintype "unspecified"))
    )
    (net (code "60") (name "Net-(Q6-G)") (class "Default")
      (node (ref "OCTO06") (pin "4") (pinfunction "4_4") (pintype "input"))
      (node (ref "Q6") (pin "3") (pinfunction "G_3") (pintype "unspecified"))
    )
    (net (code "61") (name "Net-(Q7-G)") (class "Default")
      (node (ref "OCTO07") (pin "4") (pinfunction "4_4") (pintype "input"))
      (node (ref "Q7") (pin "3") (pinfunction "G_3") (pintype "unspecified"))
    )
    (net (code "62") (name "Net-(Q8-B)") (class "Default")
      (node (ref "OCTO05") (pin "4") (pinfunction "4_4") (pintype "unspecified"))
      (node (ref "Q8") (pin "2") (pinfunction "B_2") (pintype "unspecified"))
      (node (ref "R14") (pin "2") (pinfunction "2_2") (pintype "unspecified"))
    )
    (net (code "63") (name "Net-(RELAY01-Pad2)") (class "Default")
      (node (ref "RELAY01") (pin "2") (pinfunction "2_2") (pintype "unspecified"))
      (node (ref "U9") (pin "2") (pinfunction "2_2") (pintype "unspecified"))
    )
    (net (code "64") (name "Net-(RELAY02-Pad2)") (class "Default")
      (node (ref "RELAY02") (pin "2") (pinfunction "2_2") (pintype "unspecified"))
      (node (ref "U9") (pin "1") (pinfunction "1_1") (pintype "unspecified"))
    )
    (net (code "65") (name "Net-(RELAY03-Pad2)") (class "Default")
      (node (ref "RELAY03") (pin "2") (pinfunction "2_2") (pintype "unspecified"))
      (node (ref "U10") (pin "3") (pinfunction "3_3") (pintype "unspecified"))
    )
    (net (code "66") (name "Net-(RELAY04-Pad2)") (class "Default")
      (node (ref "RELAY04") (pin "2") (pinfunction "2_2") (pintype "unspecified"))
      (node (ref "U10") (pin "2") (pinfunction "2_2") (pintype "unspecified"))
    )
    (net (code "67") (name "Net-(U5-GPIO1)") (class "Default")
      (node (ref "GPIO") (pin "2") (pinfunction "2_2") (pintype "input"))
      (node (ref "U5") (pin "6") (pinfunction "GPIO1_6") (pintype "unspecified"))
    )
    (net (code "68") (name "Net-(U5-GPIO2)") (class "Default")
      (node (ref "GPIO") (pin "1") (pinfunction "1_1") (pintype "input"))
      (node (ref "U5") (pin "4") (pinfunction "GPIO2_4") (pintype "unspecified"))
    )
    (net (code "69") (name "unconnected-(OCTO05-NC-Pad3)") (class "Default")
      (node (ref "OCTO05") (pin "3") (pinfunction "NC_3") (pintype "unspecified+no_connect"))
    )
    (net (code "70") (name "unconnected-(OCTO05-Pad6)") (class "Default")
      (node (ref "OCTO05") (pin "6") (pinfunction "6_6") (pintype "unspecified+no_connect"))
    )
    (net (code "71") (name "unconnected-(OCTO06-NC-Pad3)") (class "Default")
      (node (ref "OCTO06") (pin "3") (pinfunction "NC_3") (pintype "unspecified+no_connect"))
    )
    (net (code "72") (name "unconnected-(OCTO06-NC-Pad5)") (class "Default")
      (node (ref "OCTO06") (pin "5") (pinfunction "NC_5") (pintype "unspecified+no_connect"))
    )
    (net (code "73") (name "unconnected-(OCTO07-NC-Pad3)") (class "Default")
      (node (ref "OCTO07") (pin "3") (pinfunction "NC_3") (pintype "unspecified+no_connect"))
    )
    (net (code "74") (name "unconnected-(OCTO07-NC-Pad5)") (class "Default")
      (node (ref "OCTO07") (pin "5") (pinfunction "NC_5") (pintype "unspecified+no_connect"))
    )
    (net (code "75") (name "unconnected-(U4-EN-Pad1)") (class "Default")
      (node (ref "U4") (pin "1") (pinfunction "EN_1") (pintype "unspecified+no_connect"))
    )
    (net (code "76") (name "unconnected-(U4-STATE-Pad6)") (class "Default")
      (node (ref "U4") (pin "6") (pinfunction "STATE_6") (pintype "unspecified+no_connect"))
    )
    (net (code "77") (name "unconnected-(U5-RESET-Pad5)") (class "Default")
      (node (ref "U5") (pin "5") (pinfunction "RESET_5") (pintype "unspecified+no_connect"))
    )
    (net (code "78") (name "unconnected-(U6-AREF-Pad18)") (class "Default")
      (node (ref "U6") (pin "18") (pinfunction "AREF_18") (pintype "unspecified+no_connect"))
    )
    (net (code "79") (name "unconnected-(U6-D0{slash}RX-Pad2)") (class "Default")
      (node (ref "U6") (pin "2") (pinfunction "D0/RX_2") (pintype "unspecified+no_connect"))
    )
    (net (code "80") (name "unconnected-(U6-RESET-Pad3)") (class "Default")
      (node (ref "U6") (pin "3") (pinfunction "RESET_3") (pintype "unspecified+no_connect"))
    )
    (net (code "81") (name "unconnected-(U6-RESET-Pad28)") (class "Default")
      (node (ref "U6") (pin "28") (pinfunction "RESET_28") (pintype "unspecified+no_connect"))
    )
    (net (code "82") (name "unconnected-(U10-Pad1)") (class "Default")
      (node (ref "U10") (pin "1") (pinfunction "1_1") (pintype "unspecified+no_connect"))
    )
  )
)
